# STC51.net
KiCad netlist of a schematic drawn in Altium Designer
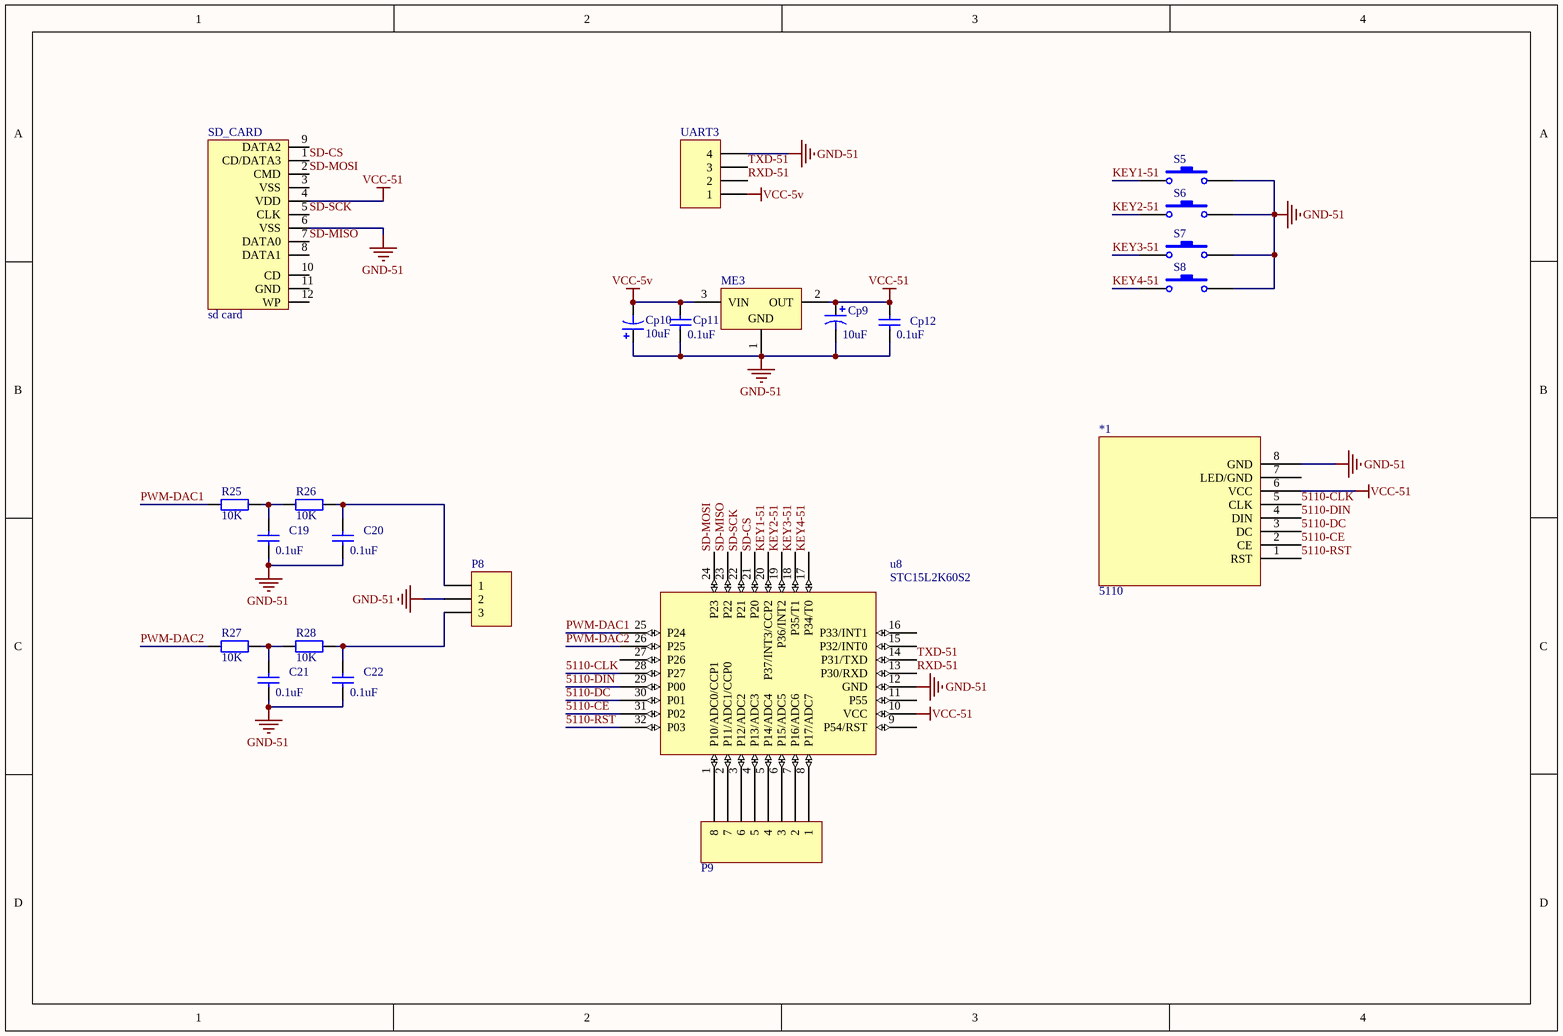
[diagram p0: STC51.SchDoc]

(export (version "E")
  (design (tool "Eeschema 10.0.6"))
  (components
    (comp (ref "*1") (value "5110") (footprint "5110") (libsource (lib "5110") (part "5110")))
    (comp (ref "C19")
      (value "0.1uF")
      (footprint "0805s")
      (description "Capacitor")
      (fields (field (name "Comment") "Cap") (field (name "PUBLISHER") "Altium Limited"))
      (libsource (lib "Miscellaneous Devices") (part "Cap"))
    )
    (comp (ref "C20")
      (value "0.1uF")
      (footprint "0805s")
      (description "Capacitor")
      (fields (field (name "Comment") "Cap") (field (name "PUBLISHER") "Altium Limited"))
      (libsource (lib "Miscellaneous Devices") (part "Cap"))
    )
    (comp (ref "C21")
      (value "0.1uF")
      (footprint "0805s")
      (description "Capacitor")
      (fields (field (name "Comment") "Cap") (field (name "PUBLISHER") "Altium Limited"))
      (libsource (lib "Miscellaneous Devices") (part "Cap"))
    )
    (comp (ref "C22")
      (value "0.1uF")
      (footprint "0805s")
      (description "Capacitor")
      (fields (field (name "Comment") "Cap") (field (name "PUBLISHER") "Altium Limited"))
      (libsource (lib "Miscellaneous Devices") (part "Cap"))
    )
    (comp (ref "Cp9")
      (value "10uF")
      (footprint "3216")
      (description "Polarized Capacitor (Radial)")
      (fields (field (name "Comment") "Cap Pol1") (field (name "PUBLISHER") "Altium Limited"))
      (libsource (lib "Miscellaneous Devices") (part "Cap Pol1"))
    )
    (comp (ref "Cp10")
      (value "10uF")
      (footprint "3216")
      (description "Polarized Capacitor (Radial)")
      (fields (field (name "Comment") "Cap Pol1") (field (name "PUBLISHER") "Altium Limited"))
      (libsource (lib "Miscellaneous Devices") (part "Cap Pol1"))
    )
    (comp (ref "Cp11")
      (value "0.1uF")
      (footprint "0805")
      (description "Capacitor")
      (fields (field (name "Comment") "Cap") (field (name "PUBLISHER") "Altium Limited"))
      (libsource (lib "Miscellaneous Devices") (part "Cap"))
    )
    (comp (ref "Cp12")
      (value "0.1uF")
      (footprint "0805")
      (description "Capacitor")
      (fields (field (name "Comment") "Cap") (field (name "PUBLISHER") "Altium Limited"))
      (libsource (lib "Miscellaneous Devices") (part "Cap"))
    )
    (comp (ref "ME3")
      (value "Volt Reg")
      (footprint "SOT-23")
      (description "Voltage Regulator")
      (fields (field (name "PUBLISHER") "Altium Limited"))
      (libsource (lib "Miscellaneous Devices") (part "Volt Reg"))
    )
    (comp (ref "P8")
      (value "Header 3")
      (footprint "HDR1X3")
      (description "Header, 3-Pin")
      (fields (field (name "PUBLISHER") "Altium Limited"))
      (libsource (lib "Miscellaneous Connectors") (part "Header 3"))
    )
    (comp (ref "P9")
      (value "Header 8")
      (footprint "HDR1X8")
      (description "Header, 8-Pin")
      (fields (field (name "PUBLISHER") "Altium Limited"))
      (libsource (lib "Miscellaneous Connectors") (part "Header 8"))
    )
    (comp (ref "R25")
      (value "10K")
      (footprint "0805s")
      (description "Resistor")
      (fields (field (name "Comment") "Res2") (field (name "PUBLISHER") "Altium Limited"))
      (libsource (lib "Miscellaneous Devices") (part "Res2"))
    )
    (comp (ref "R26")
      (value "10K")
      (footprint "0805s")
      (description "Resistor")
      (fields (field (name "Comment") "Res2") (field (name "PUBLISHER") "Altium Limited"))
      (libsource (lib "Miscellaneous Devices") (part "Res2"))
    )
    (comp (ref "R27")
      (value "10K")
      (footprint "0805s")
      (description "Resistor")
      (fields (field (name "Comment") "Res2") (field (name "PUBLISHER") "Altium Limited"))
      (libsource (lib "Miscellaneous Devices") (part "Res2"))
    )
    (comp (ref "R28")
      (value "10K")
      (footprint "0805s")
      (description "Resistor")
      (fields (field (name "Comment") "Res2") (field (name "PUBLISHER") "Altium Limited"))
      (libsource (lib "Miscellaneous Devices") (part "Res2"))
    )
    (comp (ref "S5")
      (value "SW-PB")
      (footprint "按键")
      (description "Switch")
      (fields (field (name "PUBLISHER") "Altium Limited"))
      (libsource (lib "Miscellaneous Devices") (part "SW-PB"))
    )
    (comp (ref "S6")
      (value "SW-PB")
      (footprint "按键")
      (description "Switch")
      (fields (field (name "PUBLISHER") "Altium Limited"))
      (libsource (lib "Miscellaneous Devices") (part "SW-PB"))
    )
    (comp (ref "S7")
      (value "SW-PB")
      (footprint "按键")
      (description "Switch")
      (fields (field (name "PUBLISHER") "Altium Limited"))
      (libsource (lib "Miscellaneous Devices") (part "SW-PB"))
    )
    (comp (ref "S8")
      (value "SW-PB")
      (footprint "按键")
      (description "Switch")
      (fields (field (name "PUBLISHER") "Altium Limited"))
      (libsource (lib "Miscellaneous Devices") (part "SW-PB"))
    )
    (comp (ref "SD_CARD")
      (value "sd card")
      (footprint "SD卡")
      (libsource (lib "Explorer STM32F407封装库") (part "sd card"))
    )
    (comp (ref "u8")
      (value "STC15L2K60S2")
      (footprint "LQFP-32")
      (libsource (lib "AHRS") (part "STC15L2K60S2"))
    )
    (comp (ref "UART3")
      (value "Header 4")
      (footprint "HDR1X4")
      (description "Header, 4-Pin")
      (fields (field (name "PUBLISHER") "Altium Limited"))
      (libsource (lib "Miscellaneous Connectors") (part "Header 4"))
    )
  )
  (nets
    (net (code "1") (name "/5110-CE") (class "Default")
      (node (ref "*1") (pin "2") (pinfunction "CE_2") (pintype "passive"))
      (node (ref "u8") (pin "31") (pinfunction "P02_31") (pintype "bidirectional"))
    )
    (net (code "2") (name "/5110-CLK") (class "Default")
      (node (ref "*1") (pin "5") (pinfunction "CLK_5") (pintype "passive"))
      (node (ref "u8") (pin "28") (pinfunction "P27_28") (pintype "bidirectional"))
    )
    (net (code "3") (name "/5110-DC") (class "Default")
      (node (ref "*1") (pin "3") (pinfunction "DC_3") (pintype "passive"))
      (node (ref "u8") (pin "30") (pinfunction "P01_30") (pintype "bidirectional"))
    )
    (net (code "4") (name "/5110-DIN") (class "Default")
      (node (ref "*1") (pin "4") (pinfunction "DIN_4") (pintype "passive"))
      (node (ref "u8") (pin "29") (pinfunction "P00_29") (pintype "bidirectional"))
    )
    (net (code "5") (name "/5110-RST") (class "Default")
      (node (ref "*1") (pin "1") (pinfunction "RST_1") (pintype "passive"))
      (node (ref "u8") (pin "32") (pinfunction "P03_32") (pintype "bidirectional"))
    )
    (net (code "6") (name "/KEY1-51") (class "Default")
      (node (ref "S5") (pin "1") (pinfunction "1_1") (pintype "passive"))
      (node (ref "u8") (pin "20") (pinfunction "P37/INT3/CCP2_20") (pintype "bidirectional"))
    )
    (net (code "7") (name "/KEY2-51") (class "Default")
      (node (ref "S6") (pin "1") (pinfunction "1_1") (pintype "passive"))
      (node (ref "u8") (pin "19") (pinfunction "P36/INT2_19") (pintype "bidirectional"))
    )
    (net (code "8") (name "/KEY3-51") (class "Default")
      (node (ref "S7") (pin "1") (pinfunction "1_1") (pintype "passive"))
      (node (ref "u8") (pin "18") (pinfunction "P35/T1_18") (pintype "bidirectional"))
    )
    (net (code "9") (name "/KEY4-51") (class "Default")
      (node (ref "S8") (pin "1") (pinfunction "1_1") (pintype "passive"))
      (node (ref "u8") (pin "17") (pinfunction "P34/T0_17") (pintype "bidirectional"))
    )
    (net (code "10") (name "/PWM-DAC1") (class "Default")
      (node (ref "R25") (pin "2") (pinfunction "2_2") (pintype "passive"))
      (node (ref "u8") (pin "25") (pinfunction "P24_25") (pintype "bidirectional"))
    )
    (net (code "11") (name "/PWM-DAC2") (class "Default")
      (node (ref "R27") (pin "2") (pinfunction "2_2") (pintype "passive"))
      (node (ref "u8") (pin "26") (pinfunction "P25_26") (pintype "bidirectional"))
    )
    (net (code "12") (name "/RXD-51") (class "Default")
      (node (ref "UART3") (pin "2") (pinfunction "2_2") (pintype "passive"))
      (node (ref "u8") (pin "13") (pinfunction "P30/RXD_13") (pintype "bidirectional"))
    )
    (net (code "13") (name "/SD-CS") (class "Default")
      (node (ref "SD_CARD") (pin "1") (pinfunction "CD/DATA3_1") (pintype "passive"))
      (node (ref "u8") (pin "21") (pinfunction "P20_21") (pintype "bidirectional"))
    )
    (net (code "14") (name "/SD-MISO") (class "Default")
      (node (ref "SD_CARD") (pin "7") (pinfunction "DATA0_7") (pintype "passive"))
      (node (ref "u8") (pin "23") (pinfunction "P22_23") (pintype "bidirectional"))
    )
    (net (code "15") (name "/SD-MOSI") (class "Default")
      (node (ref "SD_CARD") (pin "2") (pinfunction "CMD_2") (pintype "passive"))
      (node (ref "u8") (pin "24") (pinfunction "P23_24") (pintype "bidirectional"))
    )
    (net (code "16") (name "/SD-SCK") (class "Default")
      (node (ref "SD_CARD") (pin "5") (pinfunction "CLK_5") (pintype "passive"))
      (node (ref "u8") (pin "22") (pinfunction "P21_22") (pintype "bidirectional"))
    )
    (net (code "17") (name "/TXD-51") (class "Default")
      (node (ref "UART3") (pin "3") (pinfunction "3_3") (pintype "passive"))
      (node (ref "u8") (pin "14") (pinfunction "P31/TXD_14") (pintype "bidirectional"))
    )
    (net (code "18") (name "GND-51") (class "Default")
      (node (ref "*1") (pin "8") (pinfunction "GND_8") (pintype "passive"))
      (node (ref "C19") (pin "1") (pinfunction "1_1") (pintype "passive"))
      (node (ref "C20") (pin "1") (pinfunction "1_1") (pintype "passive"))
      (node (ref "C21") (pin "1") (pinfunction "1_1") (pintype "passive"))
      (node (ref "C22") (pin "1") (pinfunction "1_1") (pintype "passive"))
      (node (ref "Cp10") (pin "1") (pinfunction "1_1") (pintype "passive"))
      (node (ref "Cp11") (pin "1") (pinfunction "1_1") (pintype "passive"))
      (node (ref "Cp12") (pin "1") (pinfunction "1_1") (pintype "passive"))
      (node (ref "Cp9") (pin "2") (pinfunction "2_2") (pintype "passive"))
      (node (ref "ME3") (pin "1") (pinfunction "GND_1") (pintype "passive"))
      (node (ref "P8") (pin "2") (pinfunction "2_2") (pintype "passive"))
      (node (ref "S5") (pin "2") (pinfunction "2_2") (pintype "passive"))
      (node (ref "S6") (pin "2") (pinfunction "2_2") (pintype "passive"))
      (node (ref "S7") (pin "2") (pinfunction "2_2") (pintype "passive"))
      (node (ref "S8") (pin "2") (pinfunction "2_2") (pintype "passive"))
      (node (ref "SD_CARD") (pin "6") (pinfunction "VSS_6") (pintype "passive"))
      (node (ref "UART3") (pin "4") (pinfunction "4_4") (pintype "passive"))
      (node (ref "u8") (pin "12") (pinfunction "GND_12") (pintype "bidirectional"))
    )
    (net (code "19") (name "Net-(C19-Pad2)") (class "Default")
      (node (ref "C19") (pin "2") (pinfunction "2_2") (pintype "passive"))
      (node (ref "R25") (pin "1") (pinfunction "1_1") (pintype "passive"))
      (node (ref "R26") (pin "2") (pinfunction "2_2") (pintype "passive"))
    )
    (net (code "20") (name "Net-(C20-Pad2)") (class "Default")
      (node (ref "C20") (pin "2") (pinfunction "2_2") (pintype "passive"))
      (node (ref "P8") (pin "1") (pinfunction "1_1") (pintype "passive"))
      (node (ref "R26") (pin "1") (pinfunction "1_1") (pintype "passive"))
    )
    (net (code "21") (name "Net-(C21-Pad2)") (class "Default")
      (node (ref "C21") (pin "2") (pinfunction "2_2") (pintype "passive"))
      (node (ref "R27") (pin "1") (pinfunction "1_1") (pintype "passive"))
      (node (ref "R28") (pin "2") (pinfunction "2_2") (pintype "passive"))
    )
    (net (code "22") (name "Net-(C22-Pad2)") (class "Default")
      (node (ref "C22") (pin "2") (pinfunction "2_2") (pintype "passive"))
      (node (ref "P8") (pin "3") (pinfunction "3_3") (pintype "passive"))
      (node (ref "R28") (pin "1") (pinfunction "1_1") (pintype "passive"))
    )
    (net (code "23") (name "Net-(u8-P10{slash}ADC0{slash}CCP1)") (class "Default")
      (node (ref "P9") (pin "8") (pinfunction "8_8") (pintype "passive"))
      (node (ref "u8") (pin "1") (pinfunction "P10/ADC0/CCP1_1") (pintype "bidirectional"))
    )
    (net (code "24") (name "Net-(u8-P11{slash}ADC1{slash}CCP0)") (class "Default")
      (node (ref "P9") (pin "7") (pinfunction "7_7") (pintype "passive"))
      (node (ref "u8") (pin "2") (pinfunction "P11/ADC1/CCP0_2") (pintype "bidirectional"))
    )
    (net (code "25") (name "Net-(u8-P12{slash}ADC2)") (class "Default")
      (node (ref "P9") (pin "6") (pinfunction "6_6") (pintype "passive"))
      (node (ref "u8") (pin "3") (pinfunction "P12/ADC2_3") (pintype "bidirectional"))
    )
    (net (code "26") (name "Net-(u8-P13{slash}ADC3)") (class "Default")
      (node (ref "P9") (pin "5") (pinfunction "5_5") (pintype "passive"))
      (node (ref "u8") (pin "4") (pinfunction "P13/ADC3_4") (pintype "bidirectional"))
    )
    (net (code "27") (name "Net-(u8-P14{slash}ADC4)") (class "Default")
      (node (ref "P9") (pin "4") (pinfunction "4_4") (pintype "passive"))
      (node (ref "u8") (pin "5") (pinfunction "P14/ADC4_5") (pintype "bidirectional"))
    )
    (net (code "28") (name "Net-(u8-P15{slash}ADC5)") (class "Default")
      (node (ref "P9") (pin "3") (pinfunction "3_3") (pintype "passive"))
      (node (ref "u8") (pin "6") (pinfunction "P15/ADC5_6") (pintype "bidirectional"))
    )
    (net (code "29") (name "Net-(u8-P16{slash}ADC6)") (class "Default")
      (node (ref "P9") (pin "2") (pinfunction "2_2") (pintype "passive"))
      (node (ref "u8") (pin "7") (pinfunction "P16/ADC6_7") (pintype "bidirectional"))
    )
    (net (code "30") (name "Net-(u8-P17{slash}ADC7)") (class "Default")
      (node (ref "P9") (pin "1") (pinfunction "1_1") (pintype "passive"))
      (node (ref "u8") (pin "8") (pinfunction "P17/ADC7_8") (pintype "bidirectional"))
    )
    (net (code "31") (name "VCC-5v") (class "Default")
      (node (ref "Cp10") (pin "2") (pinfunction "2_2") (pintype "passive"))
      (node (ref "Cp11") (pin "2") (pinfunction "2_2") (pintype "passive"))
      (node (ref "ME3") (pin "3") (pinfunction "VIN_3") (pintype "passive"))
      (node (ref "UART3") (pin "1") (pinfunction "1_1") (pintype "passive"))
    )
    (net (code "32") (name "VCC-51") (class "Default")
      (node (ref "*1") (pin "6") (pinfunction "VCC_6") (pintype "passive"))
      (node (ref "Cp12") (pin "2") (pinfunction "2_2") (pintype "passive"))
      (node (ref "Cp9") (pin "1") (pinfunction "1_1") (pintype "passive"))
      (node (ref "ME3") (pin "2") (pinfunction "OUT_2") (pintype "passive"))
      (node (ref "SD_CARD") (pin "4") (pinfunction "VDD_4") (pintype "passive"))
      (node (ref "u8") (pin "10") (pinfunction "VCC_10") (pintype "bidirectional"))
    )
    (net (code "33") (name "unconnected-(*1-LED{slash}GND-Pad7)") (class "Default")
      (node (ref "*1") (pin "7") (pinfunction "LED/GND_7") (pintype "passive"))
    )
    (net (code "34") (name "unconnected-(SD_CARD-CD-Pad10)") (class "Default")
      (node (ref "SD_CARD") (pin "10") (pinfunction "CD_10") (pintype "passive"))
    )
    (net (code "35") (name "unconnected-(SD_CARD-DATA1-Pad8)") (class "Default")
      (node (ref "SD_CARD") (pin "8") (pinfunction "DATA1_8") (pintype "passive"))
    )
    (net (code "36") (name "unconnected-(SD_CARD-DATA2-Pad9)") (class "Default")
      (node (ref "SD_CARD") (pin "9") (pinfunction "DATA2_9") (pintype "passive"))
    )
    (net (code "37") (name "unconnected-(SD_CARD-GND-Pad11)") (class "Default")
      (node (ref "SD_CARD") (pin "11") (pinfunction "GND_11") (pintype "passive"))
    )
    (net (code "38") (name "unconnected-(SD_CARD-VSS-Pad3)") (class "Default")
      (node (ref "SD_CARD") (pin "3") (pinfunction "VSS_3") (pintype "passive"))
    )
    (net (code "39") (name "unconnected-(SD_CARD-WP-Pad12)") (class "Default")
      (node (ref "SD_CARD") (pin "12") (pinfunction "WP_12") (pintype "passive"))
    )
    (net (code "40") (name "unconnected-(u8-P26-Pad27)") (class "Default")
      (node (ref "u8") (pin "27") (pinfunction "P26_27") (pintype "bidirectional"))
    )
    (net (code "41") (name "unconnected-(u8-P32{slash}INT0-Pad15)") (class "Default")
      (node (ref "u8") (pin "15") (pinfunction "P32/INT0_15") (pintype "bidirectional"))
    )
    (net (code "42") (name "unconnected-(u8-P33{slash}INT1-Pad16)") (class "Default")
      (node (ref "u8") (pin "16") (pinfunction "P33/INT1_16") (pintype "bidirectional"))
    )
    (net (code "43") (name "unconnected-(u8-P54{slash}RST-Pad9)") (class "Default")
      (node (ref "u8") (pin "9") (pinfunction "P54/RST_9") (pintype "bidirectional"))
    )
    (net (code "44") (name "unconnected-(u8-P55-Pad11)") (class "Default")
      (node (ref "u8") (pin "11") (pinfunction "P55_11") (pintype "bidirectional"))
    )
  )
)
